# DeepSix.net
KiCad netlist of a schematic drawn in EAGLE
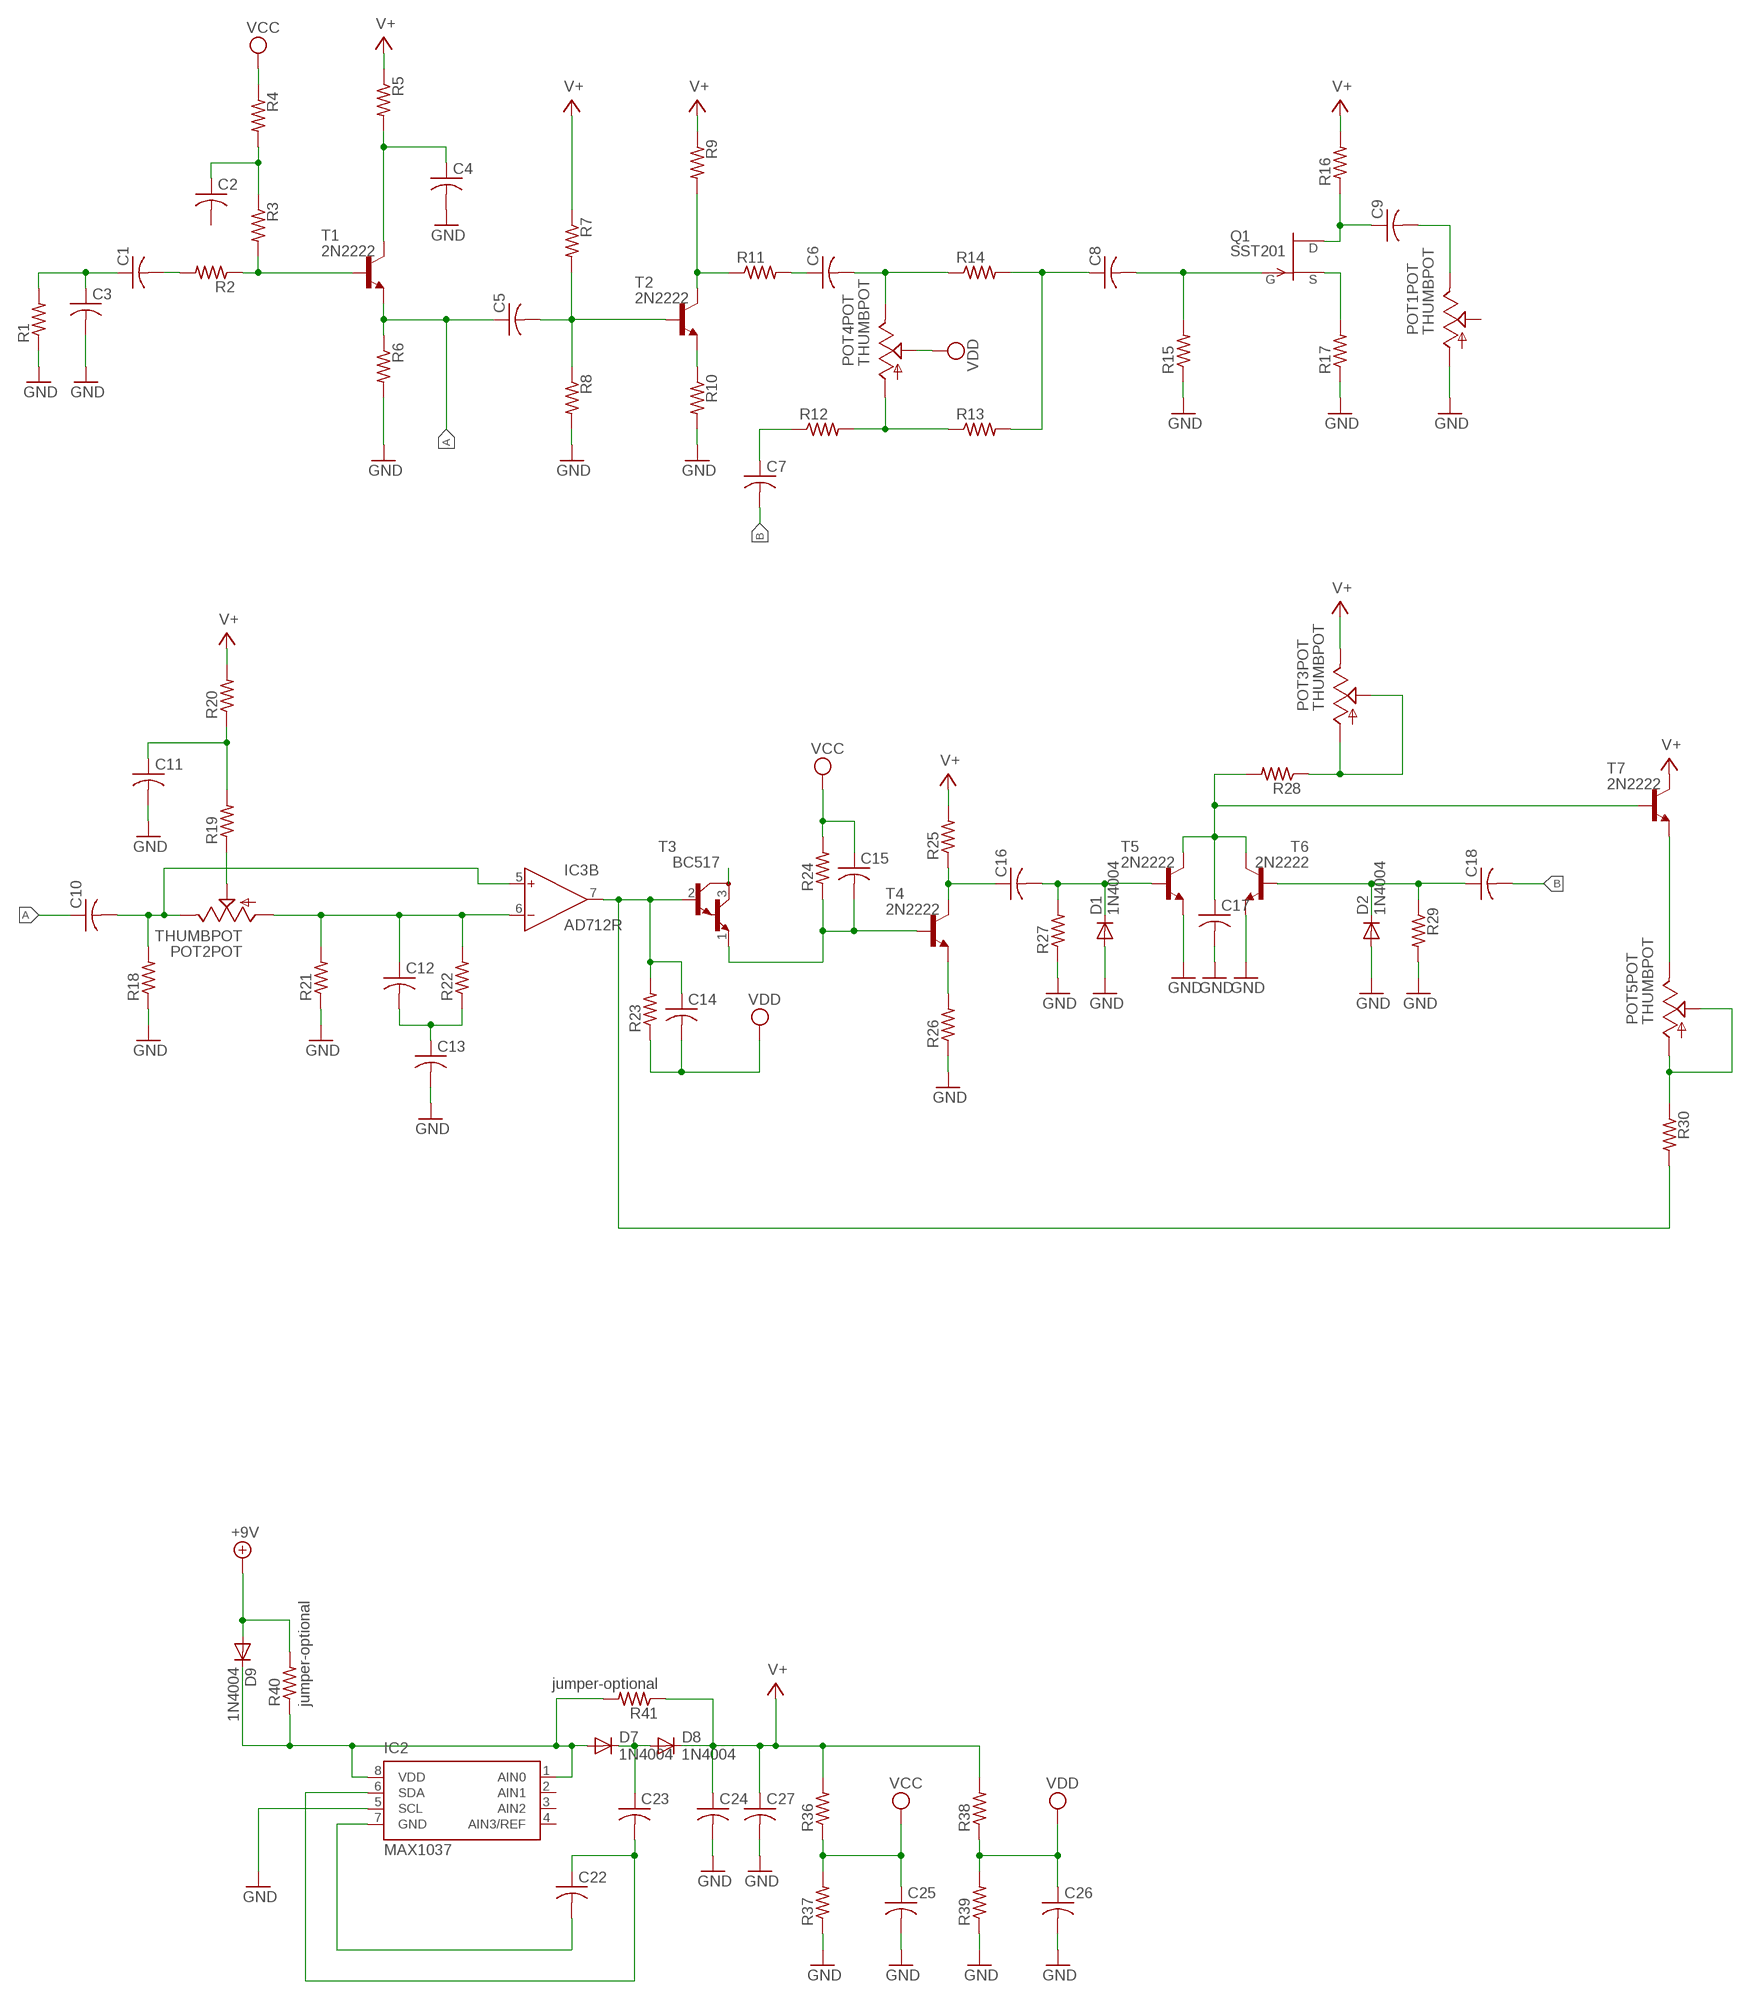
[diagram p0: schematic, sheet 1]

(export (version "E")
  (design (tool "Eeschema 10.0.6"))
  (components
    (comp (ref "C1")
      (value "C-USC0603")
      (footprint "eagle-import:C0603")
      (libsource (lib "eagle-import") (part "C-USC0603"))
    )
    (comp (ref "C2")
      (value "C-USC0603")
      (footprint "eagle-import:C0603")
      (libsource (lib "eagle-import") (part "C-USC0603"))
    )
    (comp (ref "C3")
      (value "C-USC0603")
      (footprint "eagle-import:C0603")
      (libsource (lib "eagle-import") (part "C-USC0603"))
    )
    (comp (ref "C4")
      (value "C-USC0603")
      (footprint "eagle-import:C0603")
      (libsource (lib "eagle-import") (part "C-USC0603"))
    )
    (comp (ref "C5")
      (value "C-USC0603")
      (footprint "eagle-import:C0603")
      (libsource (lib "eagle-import") (part "C-USC0603"))
    )
    (comp (ref "C6")
      (value "C-USC0603")
      (footprint "eagle-import:C0603")
      (libsource (lib "eagle-import") (part "C-USC0603"))
    )
    (comp (ref "C7")
      (value "C-USC0603")
      (footprint "eagle-import:C0603")
      (libsource (lib "eagle-import") (part "C-USC0603"))
    )
    (comp (ref "C8")
      (value "C-USC0603")
      (footprint "eagle-import:C0603")
      (libsource (lib "eagle-import") (part "C-USC0603"))
    )
    (comp (ref "C9")
      (value "C-USC0603")
      (footprint "eagle-import:C0603")
      (libsource (lib "eagle-import") (part "C-USC0603"))
    )
    (comp (ref "C10")
      (value "C-USC0603")
      (footprint "eagle-import:C0603")
      (libsource (lib "eagle-import") (part "C-USC0603"))
    )
    (comp (ref "C11")
      (value "C-USC0603")
      (footprint "eagle-import:C0603")
      (libsource (lib "eagle-import") (part "C-USC0603"))
    )
    (comp (ref "C12")
      (value "C-USC0603")
      (footprint "eagle-import:C0603")
      (libsource (lib "eagle-import") (part "C-USC0603"))
    )
    (comp (ref "C13")
      (value "C-USC0603")
      (footprint "eagle-import:C0603")
      (libsource (lib "eagle-import") (part "C-USC0603"))
    )
    (comp (ref "C14")
      (value "C-USC0603")
      (footprint "eagle-import:C0603")
      (libsource (lib "eagle-import") (part "C-USC0603"))
    )
    (comp (ref "C15")
      (value "C-USC0603")
      (footprint "eagle-import:C0603")
      (libsource (lib "eagle-import") (part "C-USC0603"))
    )
    (comp (ref "C16")
      (value "C-USC0603")
      (footprint "eagle-import:C0603")
      (libsource (lib "eagle-import") (part "C-USC0603"))
    )
    (comp (ref "C17")
      (value "C-USC0603")
      (footprint "eagle-import:C0603")
      (libsource (lib "eagle-import") (part "C-USC0603"))
    )
    (comp (ref "C18")
      (value "C-USC0603")
      (footprint "eagle-import:C0603")
      (libsource (lib "eagle-import") (part "C-USC0603"))
    )
    (comp (ref "C22")
      (value "C-USC0603")
      (footprint "eagle-import:C0603")
      (libsource (lib "eagle-import") (part "C-USC0603"))
    )
    (comp (ref "C23")
      (value "C-USC0603")
      (footprint "eagle-import:C0603")
      (libsource (lib "eagle-import") (part "C-USC0603"))
    )
    (comp (ref "C24")
      (value "C-USC0603")
      (footprint "eagle-import:C0603")
      (libsource (lib "eagle-import") (part "C-USC0603"))
    )
    (comp (ref "C25")
      (value "C-USC0603")
      (footprint "eagle-import:C0603")
      (libsource (lib "eagle-import") (part "C-USC0603"))
    )
    (comp (ref "C26")
      (value "C-USC0603")
      (footprint "eagle-import:C0603")
      (libsource (lib "eagle-import") (part "C-USC0603"))
    )
    (comp (ref "C27")
      (value "C-USC0603")
      (footprint "eagle-import:C0603")
      (libsource (lib "eagle-import") (part "C-USC0603"))
    )
    (comp (ref "D1")
      (value "1N4004")
      (footprint "eagle-import:DO41-10")
      (libsource (lib "eagle-import") (part "1N4004"))
    )
    (comp (ref "D2")
      (value "1N4004")
      (footprint "eagle-import:DO41-10")
      (libsource (lib "eagle-import") (part "1N4004"))
    )
    (comp (ref "D7")
      (value "1N4004")
      (footprint "eagle-import:DO41-10")
      (libsource (lib "eagle-import") (part "1N4004"))
    )
    (comp (ref "D8")
      (value "1N4004")
      (footprint "eagle-import:DO41-10")
      (libsource (lib "eagle-import") (part "1N4004"))
    )
    (comp (ref "D9")
      (value "1N4004")
      (footprint "eagle-import:DO41-10")
      (libsource (lib "eagle-import") (part "1N4004"))
    )
    (comp (ref "IC2")
      (value "MAX1037")
      (footprint "eagle-import:SOT23-8L")
      (fields (field (name "MF") "MAXIM") (field (name "MPN") "MAX1037EKA+T"))
      (libsource (lib "eagle-import") (part "MAX1037"))
    )
    (comp (ref "IC3")
      (value "AD712R")
      (footprint "eagle-import:SO8")
      (fields (field (name "MF") "ALTERA CORPORATION") (field (name "MPN") "AD712KRZ"))
      (libsource (lib "eagle-import") (part "AD712R"))
    )
    (comp (ref "POT1")
      (value "THUMBPOT")
      (footprint "eagle-import:THUMBWHEEL")
      (libsource (lib "eagle-import") (part "THUMBPOT"))
    )
    (comp (ref "POT2")
      (value "THUMBPOT")
      (footprint "eagle-import:THUMBWHEEL")
      (libsource (lib "eagle-import") (part "THUMBPOT"))
    )
    (comp (ref "POT3")
      (value "THUMBPOT")
      (footprint "eagle-import:THUMBWHEEL")
      (libsource (lib "eagle-import") (part "THUMBPOT"))
    )
    (comp (ref "POT4")
      (value "THUMBPOT")
      (footprint "eagle-import:THUMBWHEEL")
      (libsource (lib "eagle-import") (part "THUMBPOT"))
    )
    (comp (ref "POT5")
      (value "THUMBPOT")
      (footprint "eagle-import:THUMBWHEEL")
      (libsource (lib "eagle-import") (part "THUMBPOT"))
    )
    (comp (ref "Q1")
      (value "SST201")
      (footprint "eagle-import:SOT23")
      (libsource (lib "eagle-import") (part "?20SST1"))
    )
    (comp (ref "R1")
      (value "R-US_R0603")
      (footprint "eagle-import:R0603")
      (libsource (lib "eagle-import") (part "R-US_R0603"))
    )
    (comp (ref "R2")
      (value "R-US_R0603")
      (footprint "eagle-import:R0603")
      (libsource (lib "eagle-import") (part "R-US_R0603"))
    )
    (comp (ref "R3")
      (value "R-US_R0603")
      (footprint "eagle-import:R0603")
      (libsource (lib "eagle-import") (part "R-US_R0603"))
    )
    (comp (ref "R4")
      (value "R-US_R0603")
      (footprint "eagle-import:R0603")
      (libsource (lib "eagle-import") (part "R-US_R0603"))
    )
    (comp (ref "R5")
      (value "R-US_R0603")
      (footprint "eagle-import:R0603")
      (libsource (lib "eagle-import") (part "R-US_R0603"))
    )
    (comp (ref "R6")
      (value "R-US_R0603")
      (footprint "eagle-import:R0603")
      (libsource (lib "eagle-import") (part "R-US_R0603"))
    )
    (comp (ref "R7")
      (value "R-US_R0603")
      (footprint "eagle-import:R0603")
      (libsource (lib "eagle-import") (part "R-US_R0603"))
    )
    (comp (ref "R8")
      (value "R-US_R0603")
      (footprint "eagle-import:R0603")
      (libsource (lib "eagle-import") (part "R-US_R0603"))
    )
    (comp (ref "R9")
      (value "R-US_R0603")
      (footprint "eagle-import:R0603")
      (libsource (lib "eagle-import") (part "R-US_R0603"))
    )
    (comp (ref "R10")
      (value "R-US_R0603")
      (footprint "eagle-import:R0603")
      (libsource (lib "eagle-import") (part "R-US_R0603"))
    )
    (comp (ref "R11")
      (value "R-US_R0603")
      (footprint "eagle-import:R0603")
      (libsource (lib "eagle-import") (part "R-US_R0603"))
    )
    (comp (ref "R12")
      (value "R-US_R0603")
      (footprint "eagle-import:R0603")
      (libsource (lib "eagle-import") (part "R-US_R0603"))
    )
    (comp (ref "R13")
      (value "R-US_R0603")
      (footprint "eagle-import:R0603")
      (libsource (lib "eagle-import") (part "R-US_R0603"))
    )
    (comp (ref "R14")
      (value "R-US_R0603")
      (footprint "eagle-import:R0603")
      (libsource (lib "eagle-import") (part "R-US_R0603"))
    )
    (comp (ref "R15")
      (value "R-US_R0603")
      (footprint "eagle-import:R0603")
      (libsource (lib "eagle-import") (part "R-US_R0603"))
    )
    (comp (ref "R16")
      (value "R-US_R0603")
      (footprint "eagle-import:R0603")
      (libsource (lib "eagle-import") (part "R-US_R0603"))
    )
    (comp (ref "R17")
      (value "R-US_R0603")
      (footprint "eagle-import:R0603")
      (libsource (lib "eagle-import") (part "R-US_R0603"))
    )
    (comp (ref "R18")
      (value "R-US_R0603")
      (footprint "eagle-import:R0603")
      (libsource (lib "eagle-import") (part "R-US_R0603"))
    )
    (comp (ref "R19")
      (value "R-US_R0603")
      (footprint "eagle-import:R0603")
      (libsource (lib "eagle-import") (part "R-US_R0603"))
    )
    (comp (ref "R20")
      (value "R-US_R0603")
      (footprint "eagle-import:R0603")
      (libsource (lib "eagle-import") (part "R-US_R0603"))
    )
    (comp (ref "R21")
      (value "R-US_R0603")
      (footprint "eagle-import:R0603")
      (libsource (lib "eagle-import") (part "R-US_R0603"))
    )
    (comp (ref "R22")
      (value "R-US_R0603")
      (footprint "eagle-import:R0603")
      (libsource (lib "eagle-import") (part "R-US_R0603"))
    )
    (comp (ref "R23")
      (value "R-US_R0603")
      (footprint "eagle-import:R0603")
      (libsource (lib "eagle-import") (part "R-US_R0603"))
    )
    (comp (ref "R24")
      (value "R-US_R0603")
      (footprint "eagle-import:R0603")
      (libsource (lib "eagle-import") (part "R-US_R0603"))
    )
    (comp (ref "R25")
      (value "R-US_R0603")
      (footprint "eagle-import:R0603")
      (libsource (lib "eagle-import") (part "R-US_R0603"))
    )
    (comp (ref "R26")
      (value "R-US_R0603")
      (footprint "eagle-import:R0603")
      (libsource (lib "eagle-import") (part "R-US_R0603"))
    )
    (comp (ref "R27")
      (value "R-US_R0603")
      (footprint "eagle-import:R0603")
      (libsource (lib "eagle-import") (part "R-US_R0603"))
    )
    (comp (ref "R28")
      (value "R-US_R0603")
      (footprint "eagle-import:R0603")
      (libsource (lib "eagle-import") (part "R-US_R0603"))
    )
    (comp (ref "R29")
      (value "R-US_R0603")
      (footprint "eagle-import:R0603")
      (libsource (lib "eagle-import") (part "R-US_R0603"))
    )
    (comp (ref "R30")
      (value "R-US_R0603")
      (footprint "eagle-import:R0603")
      (libsource (lib "eagle-import") (part "R-US_R0603"))
    )
    (comp (ref "R36")
      (value "R-US_R0603")
      (footprint "eagle-import:R0603")
      (libsource (lib "eagle-import") (part "R-US_R0603"))
    )
    (comp (ref "R37")
      (value "R-US_R0603")
      (footprint "eagle-import:R0603")
      (libsource (lib "eagle-import") (part "R-US_R0603"))
    )
    (comp (ref "R38")
      (value "R-US_R0603")
      (footprint "eagle-import:R0603")
      (libsource (lib "eagle-import") (part "R-US_R0603"))
    )
    (comp (ref "R39")
      (value "R-US_R0603")
      (footprint "eagle-import:R0603")
      (libsource (lib "eagle-import") (part "R-US_R0603"))
    )
    (comp (ref "R40")
      (value "jumper-optional")
      (footprint "eagle-import:R0603")
      (libsource (lib "eagle-import") (part "R-US_R0603"))
    )
    (comp (ref "R41")
      (value "jumper-optional")
      (footprint "eagle-import:R0603")
      (libsource (lib "eagle-import") (part "R-US_R0603"))
    )
    (comp (ref "T1")
      (value "2N2222")
      (footprint "eagle-import:TO92-EBC-OVAL")
      (libsource (lib "eagle-import") (part "2N2222"))
    )
    (comp (ref "T2")
      (value "2N2222")
      (footprint "eagle-import:TO92-EBC-OVAL")
      (libsource (lib "eagle-import") (part "2N2222"))
    )
    (comp (ref "T3")
      (value "BC517")
      (footprint "eagle-import:TO92")
      (libsource (lib "eagle-import") (part "BC517"))
    )
    (comp (ref "T4")
      (value "2N2222")
      (footprint "eagle-import:TO92-EBC-OVAL")
      (libsource (lib "eagle-import") (part "2N2222"))
    )
    (comp (ref "T5")
      (value "2N2222")
      (footprint "eagle-import:TO92-EBC-OVAL")
      (libsource (lib "eagle-import") (part "2N2222"))
    )
    (comp (ref "T6")
      (value "2N2222")
      (footprint "eagle-import:TO92-EBC-OVAL")
      (libsource (lib "eagle-import") (part "2N2222"))
    )
    (comp (ref "T7")
      (value "2N2222")
      (footprint "eagle-import:TO92-EBC-OVAL")
      (libsource (lib "eagle-import") (part "2N2222"))
    )
  )
  (nets
    (net (code "1") (name "+9V") (class "Default")
      (node (ref "D9") (pin "A") (pinfunction "A_A") (pintype "passive"))
      (node (ref "R40") (pin "2") (pinfunction "2_2") (pintype "passive"))
    )
    (net (code "2") (name "A") (class "Default")
      (node (ref "C10") (pin "1") (pinfunction "1_1") (pintype "passive"))
      (node (ref "C5") (pin "1") (pinfunction "1_1") (pintype "passive"))
      (node (ref "R6") (pin "1") (pinfunction "1_1") (pintype "passive"))
      (node (ref "T1") (pin "E") (pinfunction "E_E") (pintype "passive"))
    )
    (net (code "3") (name "B") (class "Default")
      (node (ref "C18") (pin "2") (pinfunction "2_2") (pintype "passive"))
      (node (ref "C7") (pin "2") (pinfunction "2_2") (pintype "passive"))
    )
    (net (code "4") (name "GND") (class "Default")
      (node (ref "C11") (pin "2") (pinfunction "2_2") (pintype "passive"))
      (node (ref "C13") (pin "2") (pinfunction "2_2") (pintype "passive"))
      (node (ref "C17") (pin "2") (pinfunction "2_2") (pintype "passive"))
      (node (ref "C24") (pin "2") (pinfunction "2_2") (pintype "passive"))
      (node (ref "C25") (pin "2") (pinfunction "2_2") (pintype "passive"))
      (node (ref "C26") (pin "2") (pinfunction "2_2") (pintype "passive"))
      (node (ref "C27") (pin "2") (pinfunction "2_2") (pintype "passive"))
      (node (ref "C3") (pin "2") (pinfunction "2_2") (pintype "passive"))
      (node (ref "C4") (pin "2") (pinfunction "2_2") (pintype "passive"))
      (node (ref "D1") (pin "A") (pinfunction "A_A") (pintype "passive"))
      (node (ref "D2") (pin "A") (pinfunction "A_A") (pintype "passive"))
      (node (ref "IC2") (pin "5") (pinfunction "SCL_5") (pintype "input"))
      (node (ref "POT1") (pin "1") (pinfunction "A_1") (pintype "passive"))
      (node (ref "R1") (pin "1") (pinfunction "1_1") (pintype "passive"))
      (node (ref "R10") (pin "2") (pinfunction "2_2") (pintype "passive"))
      (node (ref "R15") (pin "1") (pinfunction "1_1") (pintype "passive"))
      (node (ref "R17") (pin "1") (pinfunction "1_1") (pintype "passive"))
      (node (ref "R18") (pin "1") (pinfunction "1_1") (pintype "passive"))
      (node (ref "R21") (pin "1") (pinfunction "1_1") (pintype "passive"))
      (node (ref "R26") (pin "1") (pinfunction "1_1") (pintype "passive"))
      (node (ref "R27") (pin "1") (pinfunction "1_1") (pintype "passive"))
      (node (ref "R29") (pin "2") (pinfunction "2_2") (pintype "passive"))
      (node (ref "R37") (pin "1") (pinfunction "1_1") (pintype "passive"))
      (node (ref "R39") (pin "1") (pinfunction "1_1") (pintype "passive"))
      (node (ref "R6") (pin "2") (pinfunction "2_2") (pintype "passive"))
      (node (ref "R8") (pin "2") (pinfunction "2_2") (pintype "passive"))
      (node (ref "T5") (pin "E") (pinfunction "E_E") (pintype "passive"))
      (node (ref "T6") (pin "E") (pinfunction "E_E") (pintype "passive"))
    )
    (net (code "5") (name "Net-(C1-Pad1)") (class "Default")
      (node (ref "C1") (pin "1") (pinfunction "1_1") (pintype "passive"))
      (node (ref "C3") (pin "1") (pinfunction "1_1") (pintype "passive"))
      (node (ref "R1") (pin "2") (pinfunction "2_2") (pintype "passive"))
    )
    (net (code "6") (name "Net-(C1-Pad2)") (class "Default")
      (node (ref "C1") (pin "2") (pinfunction "2_2") (pintype "passive"))
      (node (ref "R2") (pin "2") (pinfunction "2_2") (pintype "passive"))
    )
    (net (code "7") (name "Net-(C2-Pad1)") (class "Default")
      (node (ref "C2") (pin "1") (pinfunction "1_1") (pintype "passive"))
      (node (ref "R3") (pin "1") (pinfunction "1_1") (pintype "passive"))
      (node (ref "R4") (pin "2") (pinfunction "2_2") (pintype "passive"))
    )
    (net (code "8") (name "Net-(C4-Pad1)") (class "Default")
      (node (ref "C4") (pin "1") (pinfunction "1_1") (pintype "passive"))
      (node (ref "R5") (pin "2") (pinfunction "2_2") (pintype "passive"))
      (node (ref "T1") (pin "C") (pinfunction "C_C") (pintype "passive"))
    )
    (net (code "9") (name "Net-(C5-Pad2)") (class "Default")
      (node (ref "C5") (pin "2") (pinfunction "2_2") (pintype "passive"))
      (node (ref "R7") (pin "2") (pinfunction "2_2") (pintype "passive"))
      (node (ref "R8") (pin "1") (pinfunction "1_1") (pintype "passive"))
      (node (ref "T2") (pin "B") (pinfunction "B_B") (pintype "passive"))
    )
    (net (code "10") (name "Net-(C6-Pad1)") (class "Default")
      (node (ref "C6") (pin "1") (pinfunction "1_1") (pintype "passive"))
      (node (ref "R11") (pin "2") (pinfunction "2_2") (pintype "passive"))
    )
    (net (code "11") (name "Net-(C7-Pad1)") (class "Default")
      (node (ref "C7") (pin "1") (pinfunction "1_1") (pintype "passive"))
      (node (ref "R12") (pin "1") (pinfunction "1_1") (pintype "passive"))
    )
    (net (code "12") (name "Net-(C8-Pad1)") (class "Default")
      (node (ref "C8") (pin "1") (pinfunction "1_1") (pintype "passive"))
      (node (ref "R13") (pin "2") (pinfunction "2_2") (pintype "passive"))
      (node (ref "R14") (pin "2") (pinfunction "2_2") (pintype "passive"))
    )
    (net (code "13") (name "Net-(C11-Pad1)") (class "Default")
      (node (ref "C11") (pin "1") (pinfunction "1_1") (pintype "passive"))
      (node (ref "R19") (pin "2") (pinfunction "2_2") (pintype "passive"))
      (node (ref "R20") (pin "1") (pinfunction "1_1") (pintype "passive"))
    )
    (net (code "14") (name "Net-(C12-Pad2)") (class "Default")
      (node (ref "C12") (pin "2") (pinfunction "2_2") (pintype "passive"))
      (node (ref "C13") (pin "1") (pinfunction "1_1") (pintype "passive"))
      (node (ref "R22") (pin "1") (pinfunction "1_1") (pintype "passive"))
    )
    (net (code "15") (name "Net-(C16-Pad1)") (class "Default")
      (node (ref "C16") (pin "1") (pinfunction "1_1") (pintype "passive"))
      (node (ref "R25") (pin "1") (pinfunction "1_1") (pintype "passive"))
      (node (ref "T4") (pin "C") (pinfunction "C_C") (pintype "passive"))
    )
    (net (code "16") (name "Net-(C16-Pad2)") (class "Default")
      (node (ref "C16") (pin "2") (pinfunction "2_2") (pintype "passive"))
      (node (ref "D1") (pin "C") (pinfunction "C_C") (pintype "passive"))
      (node (ref "R27") (pin "2") (pinfunction "2_2") (pintype "passive"))
      (node (ref "T5") (pin "B") (pinfunction "B_B") (pintype "passive"))
    )
    (net (code "17") (name "Net-(C17-Pad1)") (class "Default")
      (node (ref "C17") (pin "1") (pinfunction "1_1") (pintype "passive"))
      (node (ref "R28") (pin "2") (pinfunction "2_2") (pintype "passive"))
      (node (ref "T5") (pin "C") (pinfunction "C_C") (pintype "passive"))
      (node (ref "T6") (pin "C") (pinfunction "C_C") (pintype "passive"))
      (node (ref "T7") (pin "B") (pinfunction "B_B") (pintype "passive"))
    )
    (net (code "18") (name "Net-(C18-Pad1)") (class "Default")
      (node (ref "C18") (pin "1") (pinfunction "1_1") (pintype "passive"))
      (node (ref "D2") (pin "C") (pinfunction "C_C") (pintype "passive"))
      (node (ref "R29") (pin "1") (pinfunction "1_1") (pintype "passive"))
      (node (ref "T6") (pin "B") (pinfunction "B_B") (pintype "passive"))
    )
    (net (code "19") (name "Net-(C23-Pad1)") (class "Default")
      (node (ref "C23") (pin "1") (pinfunction "1_1") (pintype "passive"))
      (node (ref "D7") (pin "C") (pinfunction "C_C") (pintype "passive"))
      (node (ref "D8") (pin "A") (pinfunction "A_A") (pintype "passive"))
    )
    (net (code "20") (name "Net-(IC2-AIN0)") (class "Default")
      (node (ref "D7") (pin "A") (pinfunction "A_A") (pintype "passive"))
      (node (ref "D9") (pin "C") (pinfunction "C_C") (pintype "passive"))
      (node (ref "IC2") (pin "1") (pinfunction "AIN0_1") (pintype "input"))
      (node (ref "IC2") (pin "8") (pinfunction "VDD_8") (pintype "power_in"))
      (node (ref "R40") (pin "1") (pinfunction "1_1") (pintype "passive"))
      (node (ref "R41") (pin "2") (pinfunction "2_2") (pintype "passive"))
    )
    (net (code "21") (name "Net-(IC2-GND)") (class "Default")
      (node (ref "C22") (pin "2") (pinfunction "2_2") (pintype "passive"))
      (node (ref "IC2") (pin "7") (pinfunction "GND_7") (pintype "power_in"))
    )
    (net (code "22") (name "Net-(IC2-SDA)") (class "Default")
      (node (ref "C22") (pin "1") (pinfunction "1_1") (pintype "passive"))
      (node (ref "C23") (pin "2") (pinfunction "2_2") (pintype "passive"))
      (node (ref "IC2") (pin "6") (pinfunction "SDA_6") (pintype "input"))
    )
    (net (code "23") (name "Net-(IC3B-IN+)") (class "Default")
      (node (ref "C10") (pin "2") (pinfunction "2_2") (pintype "passive"))
      (node (ref "IC3") (pin "5") (pinfunction "IN+_5") (pintype "input"))
      (node (ref "POT2") (pin "3") (pinfunction "E_3") (pintype "passive"))
      (node (ref "R18") (pin "2") (pinfunction "2_2") (pintype "passive"))
    )
    (net (code "24") (name "Net-(IC3B-IN-)") (class "Default")
      (node (ref "C12") (pin "1") (pinfunction "1_1") (pintype "passive"))
      (node (ref "IC3") (pin "6") (pinfunction "IN-_6") (pintype "input"))
      (node (ref "POT2") (pin "1") (pinfunction "A_1") (pintype "passive"))
      (node (ref "R21") (pin "2") (pinfunction "2_2") (pintype "passive"))
      (node (ref "R22") (pin "2") (pinfunction "2_2") (pintype "passive"))
    )
    (net (code "25") (name "Net-(IC3B-OUT)") (class "Default")
      (node (ref "C14") (pin "1") (pinfunction "1_1") (pintype "passive"))
      (node (ref "IC3") (pin "7") (pinfunction "OUT_7") (pintype "output"))
      (node (ref "R23") (pin "2") (pinfunction "2_2") (pintype "passive"))
      (node (ref "R30") (pin "2") (pinfunction "2_2") (pintype "passive"))
      (node (ref "T3") (pin "2") (pinfunction "B_2") (pintype "passive"))
    )
    (net (code "26") (name "Net-(POT1A-E)") (class "Default")
      (node (ref "C9") (pin "2") (pinfunction "2_2") (pintype "passive"))
      (node (ref "POT1") (pin "3") (pinfunction "E_3") (pintype "passive"))
    )
    (net (code "27") (name "Net-(POT2A-S)") (class "Default")
      (node (ref "POT2") (pin "2") (pinfunction "S_2") (pintype "passive"))
      (node (ref "R19") (pin "1") (pinfunction "1_1") (pintype "passive"))
    )
    (net (code "28") (name "Net-(POT3A-A)") (class "Default")
      (node (ref "POT3") (pin "1") (pinfunction "A_1") (pintype "passive"))
      (node (ref "POT3") (pin "2") (pinfunction "S_2") (pintype "passive"))
      (node (ref "R28") (pin "1") (pinfunction "1_1") (pintype "passive"))
    )
    (net (code "29") (name "Net-(POT4A-A)") (class "Default")
      (node (ref "POT4") (pin "1") (pinfunction "A_1") (pintype "passive"))
      (node (ref "R12") (pin "2") (pinfunction "2_2") (pintype "passive"))
      (node (ref "R13") (pin "1") (pinfunction "1_1") (pintype "passive"))
    )
    (net (code "30") (name "Net-(POT4A-E)") (class "Default")
      (node (ref "C6") (pin "2") (pinfunction "2_2") (pintype "passive"))
      (node (ref "POT4") (pin "3") (pinfunction "E_3") (pintype "passive"))
      (node (ref "R14") (pin "1") (pinfunction "1_1") (pintype "passive"))
    )
    (net (code "31") (name "Net-(POT5A-A)") (class "Default")
      (node (ref "POT5") (pin "1") (pinfunction "A_1") (pintype "passive"))
      (node (ref "POT5") (pin "2") (pinfunction "S_2") (pintype "passive"))
      (node (ref "R30") (pin "1") (pinfunction "1_1") (pintype "passive"))
    )
    (net (code "32") (name "Net-(POT5A-E)") (class "Default")
      (node (ref "POT5") (pin "3") (pinfunction "E_3") (pintype "passive"))
      (node (ref "T7") (pin "E") (pinfunction "E_E") (pintype "passive"))
    )
    (net (code "33") (name "Net-(Q1-D)") (class "Default")
      (node (ref "C9") (pin "1") (pinfunction "1_1") (pintype "passive"))
      (node (ref "Q1") (pin "1") (pinfunction "D_1") (pintype "passive"))
      (node (ref "R16") (pin "1") (pinfunction "1_1") (pintype "passive"))
    )
    (net (code "34") (name "Net-(Q1-G)") (class "Default")
      (node (ref "C8") (pin "2") (pinfunction "2_2") (pintype "passive"))
      (node (ref "Q1") (pin "3") (pinfunction "G_3") (pintype "passive"))
      (node (ref "R15") (pin "2") (pinfunction "2_2") (pintype "passive"))
    )
    (net (code "35") (name "Net-(Q1-S)") (class "Default")
      (node (ref "Q1") (pin "2") (pinfunction "S_2") (pintype "passive"))
      (node (ref "R17") (pin "2") (pinfunction "2_2") (pintype "passive"))
    )
    (net (code "36") (name "Net-(R2-Pad1)") (class "Default")
      (node (ref "R2") (pin "1") (pinfunction "1_1") (pintype "passive"))
      (node (ref "R3") (pin "2") (pinfunction "2_2") (pintype "passive"))
      (node (ref "T1") (pin "B") (pinfunction "B_B") (pintype "passive"))
    )
    (net (code "37") (name "Net-(R10-Pad1)") (class "Default")
      (node (ref "R10") (pin "1") (pinfunction "1_1") (pintype "passive"))
      (node (ref "T2") (pin "E") (pinfunction "E_E") (pintype "passive"))
    )
    (net (code "38") (name "Net-(R11-Pad1)") (class "Default")
      (node (ref "R11") (pin "1") (pinfunction "1_1") (pintype "passive"))
      (node (ref "R9") (pin "2") (pinfunction "2_2") (pintype "passive"))
      (node (ref "T2") (pin "C") (pinfunction "C_C") (pintype "passive"))
    )
    (net (code "39") (name "Net-(R26-Pad2)") (class "Default")
      (node (ref "R26") (pin "2") (pinfunction "2_2") (pintype "passive"))
      (node (ref "T4") (pin "E") (pinfunction "E_E") (pintype "passive"))
    )
    (net (code "40") (name "Net-(T3-E)") (class "Default")
      (node (ref "C15") (pin "2") (pinfunction "2_2") (pintype "passive"))
      (node (ref "R24") (pin "1") (pinfunction "1_1") (pintype "passive"))
      (node (ref "T3") (pin "1") (pinfunction "E_1") (pintype "passive"))
      (node (ref "T4") (pin "B") (pinfunction "B_B") (pintype "passive"))
    )
    (net (code "41") (name "V+") (class "Default")
      (node (ref "C24") (pin "1") (pinfunction "1_1") (pintype "passive"))
      (node (ref "C27") (pin "1") (pinfunction "1_1") (pintype "passive"))
      (node (ref "D8") (pin "C") (pinfunction "C_C") (pintype "passive"))
      (node (ref "POT3") (pin "3") (pinfunction "E_3") (pintype "passive"))
      (node (ref "R16") (pin "2") (pinfunction "2_2") (pintype "passive"))
      (node (ref "R20") (pin "2") (pinfunction "2_2") (pintype "passive"))
      (node (ref "R25") (pin "2") (pinfunction "2_2") (pintype "passive"))
      (node (ref "R36") (pin "2") (pinfunction "2_2") (pintype "passive"))
      (node (ref "R38") (pin "2") (pinfunction "2_2") (pintype "passive"))
      (node (ref "R41") (pin "1") (pinfunction "1_1") (pintype "passive"))
      (node (ref "R5") (pin "1") (pinfunction "1_1") (pintype "passive"))
      (node (ref "R7") (pin "1") (pinfunction "1_1") (pintype "passive"))
      (node (ref "R9") (pin "1") (pinfunction "1_1") (pintype "passive"))
      (node (ref "T7") (pin "C") (pinfunction "C_C") (pintype "passive"))
    )
    (net (code "42") (name "VCC") (class "Default")
      (node (ref "C15") (pin "1") (pinfunction "1_1") (pintype "passive"))
      (node (ref "C25") (pin "1") (pinfunction "1_1") (pintype "passive"))
      (node (ref "R24") (pin "2") (pinfunction "2_2") (pintype "passive"))
      (node (ref "R36") (pin "1") (pinfunction "1_1") (pintype "passive"))
      (node (ref "R37") (pin "2") (pinfunction "2_2") (pintype "passive"))
      (node (ref "R4") (pin "1") (pinfunction "1_1") (pintype "passive"))
    )
    (net (code "43") (name "VDD") (class "Default")
      (node (ref "C14") (pin "2") (pinfunction "2_2") (pintype "passive"))
      (node (ref "C26") (pin "1") (pinfunction "1_1") (pintype "passive"))
      (node (ref "POT4") (pin "2") (pinfunction "S_2") (pintype "passive"))
      (node (ref "R23") (pin "1") (pinfunction "1_1") (pintype "passive"))
      (node (ref "R38") (pin "1") (pinfunction "1_1") (pintype "passive"))
      (node (ref "R39") (pin "2") (pinfunction "2_2") (pintype "passive"))
    )
    (net (code "44") (name "unconnected-(C2-Pad2)") (class "Default")
      (node (ref "C2") (pin "2") (pinfunction "2_2") (pintype "passive"))
    )
    (net (code "45") (name "unconnected-(IC2-AIN1-Pad2)") (class "Default")
      (node (ref "IC2") (pin "2") (pinfunction "AIN1_2") (pintype "input"))
    )
    (net (code "46") (name "unconnected-(IC2-AIN2-Pad3)") (class "Default")
      (node (ref "IC2") (pin "3") (pinfunction "AIN2_3") (pintype "input"))
    )
    (net (code "47") (name "unconnected-(IC2-AIN3{slash}REF-Pad4)") (class "Default")
      (node (ref "IC2") (pin "4") (pinfunction "AIN3/REF_4") (pintype "input"))
    )
    (net (code "48") (name "unconnected-(POT1A-S-Pad2)") (class "Default")
      (node (ref "POT1") (pin "2") (pinfunction "S_2") (pintype "passive"))
    )
    (net (code "49") (name "unconnected-(T3-C-Pad3)") (class "Default")
      (node (ref "T3") (pin "3") (pinfunction "C_3") (pintype "passive"))
    )
  )
)
